# v1_0.net
KiCad netlist of a schematic drawn in Altium Designer
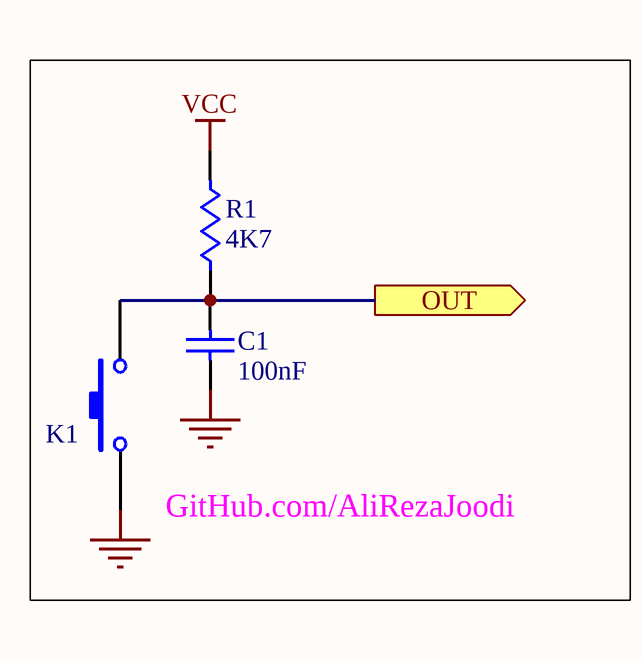
[diagram p0: v1.0.SchDoc]

(export (version "E")
  (design (tool "Eeschema 10.0.6"))
  (components
    (comp (ref "C1")
      (value "100nF")
      (footprint "CAPNTO2.54-3.56x2.03")
      (description "Capacitor")
      (fields (field (name "MANUFACTURER") "Generic Components") (field (name "PUBLISHER") "Altium Limited"))
      (libsource (lib "Miscellaneous Devices") (part "Cap"))
    )
    (comp (ref "K1")
      (value "SW-PB")
      (footprint "SPST-2_2")
      (description "Switch")
      (fields (field (name "MANUFACTURER") "Generic Components") (field (name "PUBLISHER") "Altium Limited"))
      (libsource (lib "Miscellaneous Devices") (part "SW-PB"))
    )
    (comp (ref "R1")
      (value "4K7")
      (footprint "AXIAL-0.4")
      (description "Resistor")
      (fields (field (name "MANUFACTURER") "Generic Components") (field (name "PUBLISHER") "Altium Limited"))
      (libsource (lib "Miscellaneous Devices") (part "Res1"))
    )
  )
  (nets
    (net (code "1") (name "/OUT") (class "Default")
      (node (ref "C1") (pin "1") (pinfunction "1_1") (pintype "passive"))
      (node (ref "K1") (pin "2") (pinfunction "2_2") (pintype "passive"))
      (node (ref "R1") (pin "1") (pinfunction "1_1") (pintype "passive"))
    )
    (net (code "2") (name "GND") (class "Default")
      (node (ref "C1") (pin "2") (pinfunction "2_2") (pintype "passive"))
      (node (ref "K1") (pin "1") (pinfunction "1_1") (pintype "passive"))
    )
    (net (code "3") (name "VCC") (class "Default")
      (node (ref "R1") (pin "2") (pinfunction "2_2") (pintype "passive"))
    )
  )
)
